# T_STorM32_motor_v24E.net
KiCad netlist of a schematic drawn in EAGLE
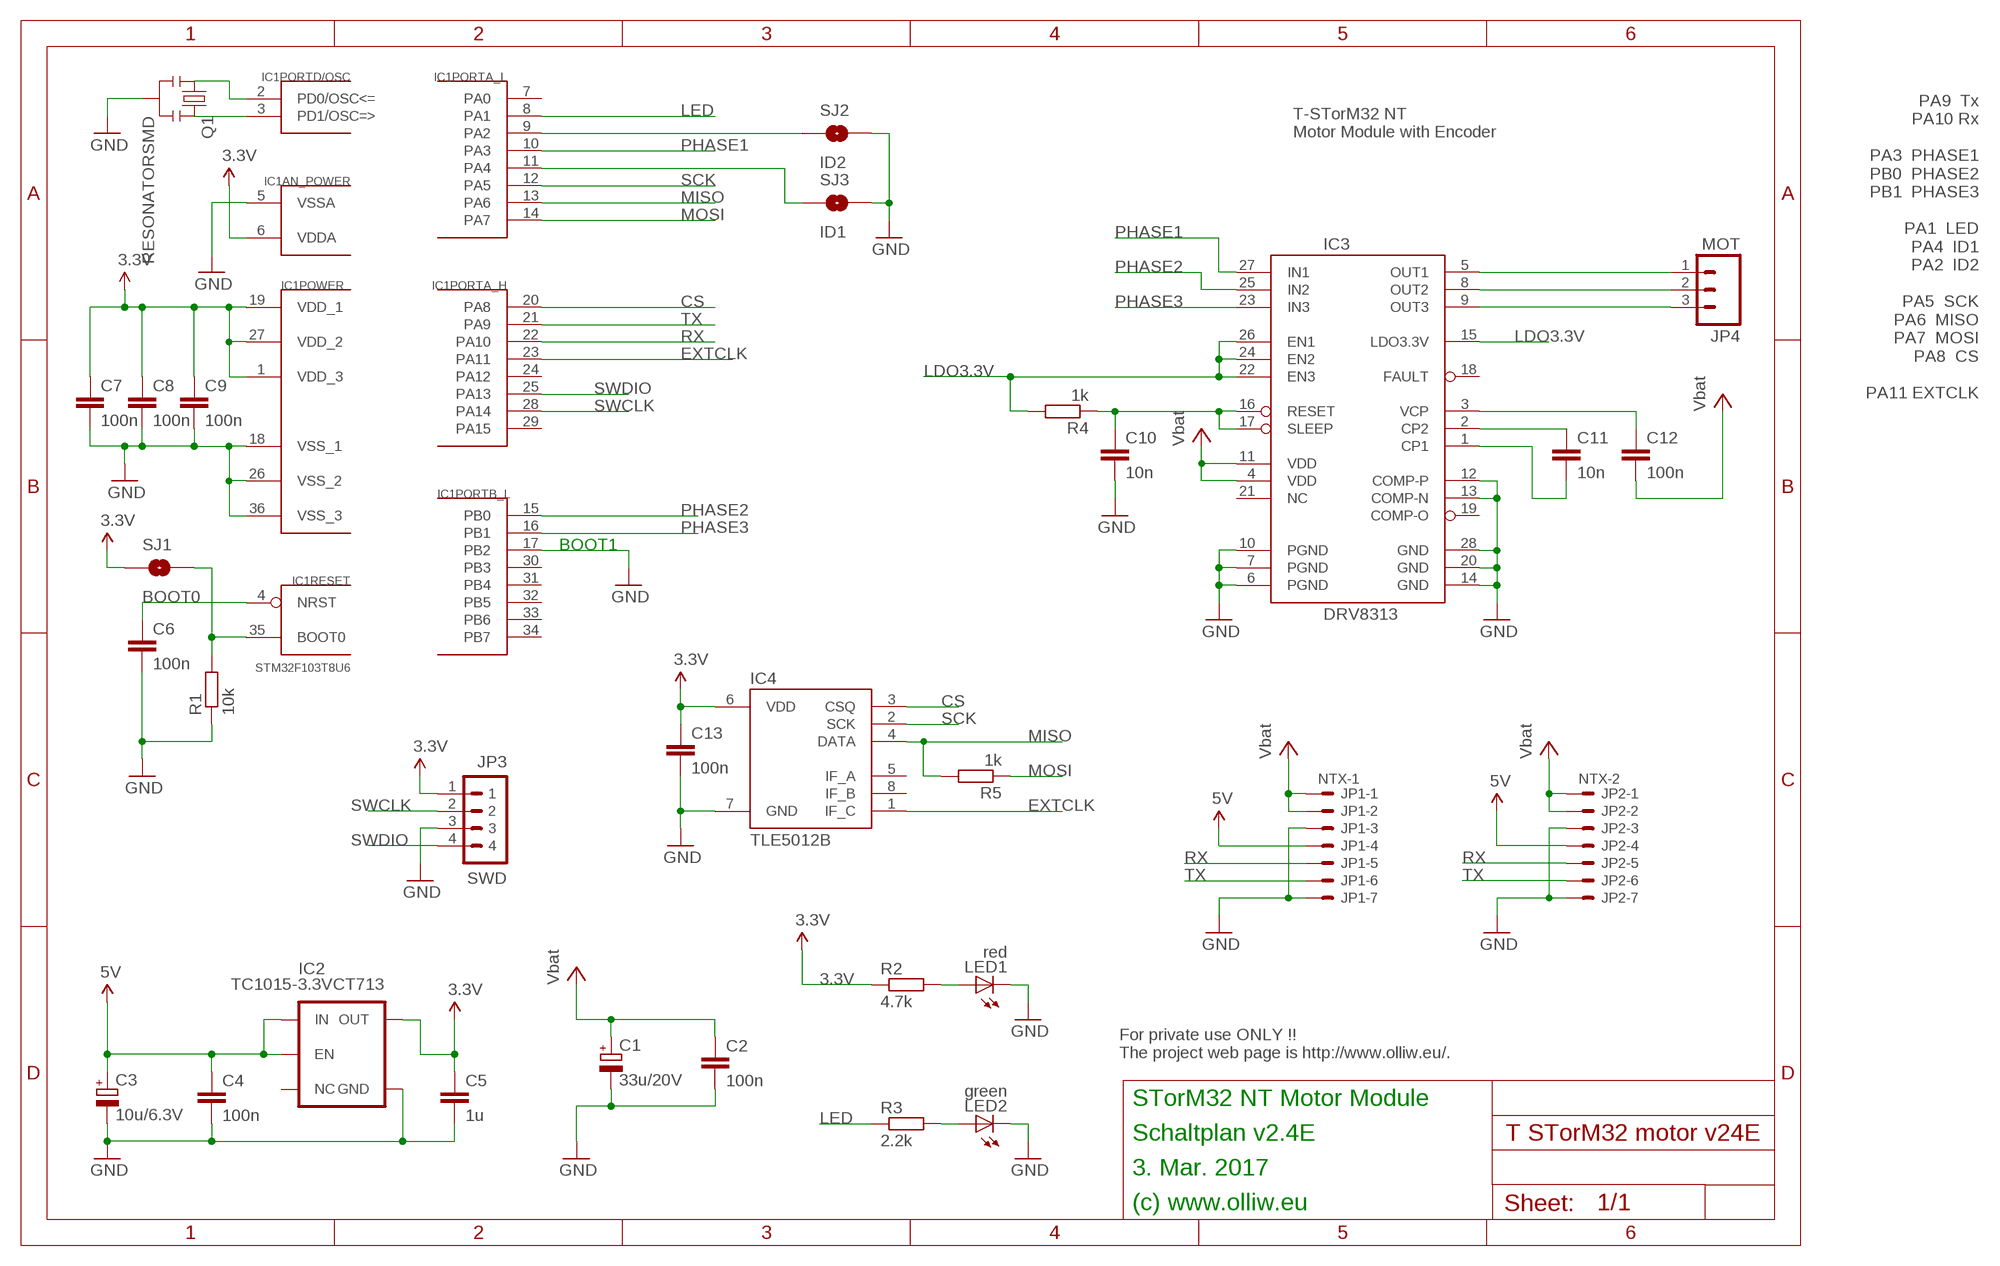
[diagram p0: schematic, sheet 1]

(export (version "E")
  (design (tool "Eeschema 10.0.6"))
  (components
    (comp (ref "C1")
      (value "33u/20V")
      (footprint "eagle-import:SMC_C")
      (libsource (lib "eagle-import") (part "CPOL-EUSMCC"))
    )
    (comp (ref "C2")
      (value "100n")
      (footprint "eagle-import:C0603")
      (libsource (lib "eagle-import") (part "C-EUC0603"))
    )
    (comp (ref "C3")
      (value "10u/6.3V")
      (footprint "eagle-import:SMC_B")
      (libsource (lib "eagle-import") (part "CPOL-EUSMCB"))
    )
    (comp (ref "C4")
      (value "100n")
      (footprint "eagle-import:C0603")
      (libsource (lib "eagle-import") (part "C-EUC0603"))
    )
    (comp (ref "C5")
      (value "1u")
      (footprint "eagle-import:C0603")
      (libsource (lib "eagle-import") (part "C-EUC0603"))
    )
    (comp (ref "C6")
      (value "100n")
      (footprint "eagle-import:C0603")
      (libsource (lib "eagle-import") (part "C-EUC0603"))
    )
    (comp (ref "C7")
      (value "100n")
      (footprint "eagle-import:C0603")
      (libsource (lib "eagle-import") (part "C-EUC0603"))
    )
    (comp (ref "C8")
      (value "100n")
      (footprint "eagle-import:C0603")
      (libsource (lib "eagle-import") (part "C-EUC0603"))
    )
    (comp (ref "C9")
      (value "100n")
      (footprint "eagle-import:C0603")
      (libsource (lib "eagle-import") (part "C-EUC0603"))
    )
    (comp (ref "C10")
      (value "10n")
      (footprint "eagle-import:C0603")
      (libsource (lib "eagle-import") (part "C-EUC0603"))
    )
    (comp (ref "C11")
      (value "10n")
      (footprint "eagle-import:C0603")
      (libsource (lib "eagle-import") (part "C-EUC0603"))
    )
    (comp (ref "C12")
      (value "100n")
      (footprint "eagle-import:C0603")
      (libsource (lib "eagle-import") (part "C-EUC0603"))
    )
    (comp (ref "C13")
      (value "100n")
      (footprint "eagle-import:C0603")
      (libsource (lib "eagle-import") (part "C-EUC0603"))
    )
    (comp (ref "IC1")
      (value "STM32F103T8U6")
      (footprint "eagle-import:VFQFPN36")
      (libsource (lib "eagle-import") (part "STM32F10XTXU6"))
    )
    (comp (ref "IC2")
      (value "TC1015-3.3VCT713")
      (footprint "eagle-import:SOT23-5")
      (libsource (lib "eagle-import") (part "V_REG_TPS76433SOT23-5"))
    )
    (comp (ref "IC3")
      (value "DRV8313")
      (footprint "eagle-import:HTSSOP28")
      (libsource (lib "eagle-import") (part "DRV8313"))
    )
    (comp (ref "IC4")
      (value "TLE5012B")
      (footprint "eagle-import:SO08")
      (libsource (lib "eagle-import") (part "TLE5012B"))
    )
    (comp (ref "JP1")
      (value "NTX-1")
      (footprint "eagle-import:SM07B-SRSS-TB")
      (libsource (lib "eagle-import") (part "?M07B-SRSS-TBS"))
    )
    (comp (ref "JP2")
      (value "NTX-2")
      (footprint "eagle-import:SM07B-SRSS-TB")
      (libsource (lib "eagle-import") (part "?M07B-SRSS-TBS"))
    )
    (comp (ref "JP3")
      (value "SWD")
      (footprint "eagle-import:4X1_1P27_OCT_BILEX")
      (libsource (lib "eagle-import") (part "P4X1_1P27-OCT_BILEX"))
    )
    (comp (ref "JP4")
      (value "MOT")
      (footprint "eagle-import:1X03")
      (libsource (lib "eagle-import") (part "M03PTH"))
    )
    (comp (ref "LED1")
      (value "red")
      (footprint "eagle-import:CHIPLED_0603")
      (libsource (lib "eagle-import") (part "LEDCHIPLED_0603"))
    )
    (comp (ref "LED2")
      (value "green")
      (footprint "eagle-import:CHIPLED_0603")
      (libsource (lib "eagle-import") (part "LEDCHIPLED_0603"))
    )
    (comp (ref "Q1")
      (value "RESONATORSMD")
      (footprint "eagle-import:RESONATOR-SMD")
      (libsource (lib "eagle-import") (part "RESONATORSMD"))
    )
    (comp (ref "R1")
      (value "10k")
      (footprint "eagle-import:R0603")
      (libsource (lib "eagle-import") (part "R-EU_R0603"))
    )
    (comp (ref "R2")
      (value "4.7k")
      (footprint "eagle-import:R0603")
      (libsource (lib "eagle-import") (part "R-EU_R0603"))
    )
    (comp (ref "R3")
      (value "2.2k")
      (footprint "eagle-import:R0603")
      (libsource (lib "eagle-import") (part "R-EU_R0603"))
    )
    (comp (ref "R4")
      (value "1k")
      (footprint "eagle-import:R0603")
      (libsource (lib "eagle-import") (part "R-EU_R0603"))
    )
    (comp (ref "R5")
      (value "1k")
      (footprint "eagle-import:R0603")
      (libsource (lib "eagle-import") (part "R-EU_R0603"))
    )
    (comp (ref "SJ1")
      (value "BOOT0")
      (footprint "eagle-import:SJ_2S-NO")
      (libsource (lib "eagle-import") (part "SOLDERJUMPERNO"))
    )
    (comp (ref "SJ2")
      (value "ID2")
      (footprint "eagle-import:SJ_2S-NO")
      (libsource (lib "eagle-import") (part "SOLDERJUMPERNO"))
    )
    (comp (ref "SJ3")
      (value "ID1")
      (footprint "eagle-import:SJ_2S-NO")
      (libsource (lib "eagle-import") (part "SOLDERJUMPERNO"))
    )
  )
  (nets
    (net (code "1") (name "/CS") (class "Default")
      (node (ref "IC1") (pin "20") (pinfunction "PA8_20") (pintype "bidirectional"))
      (node (ref "IC4") (pin "3") (pinfunction "CSQ_3") (pintype "input"))
    )
    (net (code "2") (name "/EXTCLK") (class "Default")
      (node (ref "IC1") (pin "23") (pinfunction "PA11_23") (pintype "bidirectional"))
      (node (ref "IC4") (pin "1") (pinfunction "IF_C_1") (pintype "bidirectional"))
    )
    (net (code "3") (name "/LDO3.3V") (class "Default")
      (node (ref "IC3") (pin "15") (pinfunction "LDO3.3V_15") (pintype "output"))
      (node (ref "IC3") (pin "22") (pinfunction "EN3_22") (pintype "input"))
      (node (ref "IC3") (pin "24") (pinfunction "EN2_24") (pintype "input"))
      (node (ref "IC3") (pin "26") (pinfunction "EN1_26") (pintype "input"))
      (node (ref "R4") (pin "2") (pinfunction "2_2") (pintype "passive"))
    )
    (net (code "4") (name "/LED") (class "Default")
      (node (ref "IC1") (pin "8") (pinfunction "PA1_8") (pintype "bidirectional"))
      (node (ref "R3") (pin "1") (pinfunction "1_1") (pintype "passive"))
    )
    (net (code "5") (name "/MISO") (class "Default")
      (node (ref "IC1") (pin "13") (pinfunction "PA6_13") (pintype "bidirectional"))
      (node (ref "IC4") (pin "4") (pinfunction "DATA_4") (pintype "bidirectional"))
      (node (ref "R5") (pin "2") (pinfunction "2_2") (pintype "passive"))
    )
    (net (code "6") (name "/MOSI") (class "Default")
      (node (ref "IC1") (pin "14") (pinfunction "PA7_14") (pintype "bidirectional"))
      (node (ref "R5") (pin "1") (pinfunction "1_1") (pintype "passive"))
    )
    (net (code "7") (name "/PHASE1") (class "Default")
      (node (ref "IC1") (pin "10") (pinfunction "PA3_10") (pintype "bidirectional"))
      (node (ref "IC3") (pin "27") (pinfunction "IN1_27") (pintype "input"))
    )
    (net (code "8") (name "/PHASE2") (class "Default")
      (node (ref "IC1") (pin "15") (pinfunction "PB0_15") (pintype "bidirectional"))
      (node (ref "IC3") (pin "25") (pinfunction "IN2_25") (pintype "input"))
    )
    (net (code "9") (name "/PHASE3") (class "Default")
      (node (ref "IC1") (pin "16") (pinfunction "PB1_16") (pintype "bidirectional"))
      (node (ref "IC3") (pin "23") (pinfunction "IN3_23") (pintype "input"))
    )
    (net (code "10") (name "/RX") (class "Default")
      (node (ref "IC1") (pin "22") (pinfunction "PA10_22") (pintype "bidirectional"))
      (node (ref "JP1") (pin "5") (pinfunction "S_5") (pintype "passive"))
      (node (ref "JP2") (pin "5") (pinfunction "S_5") (pintype "passive"))
    )
    (net (code "11") (name "/SCK") (class "Default")
      (node (ref "IC1") (pin "12") (pinfunction "PA5_12") (pintype "bidirectional"))
      (node (ref "IC4") (pin "2") (pinfunction "SCK_2") (pintype "input"))
    )
    (net (code "12") (name "/SWCLK") (class "Default")
      (node (ref "IC1") (pin "28") (pinfunction "PA14_28") (pintype "bidirectional"))
      (node (ref "JP3") (pin "2") (pinfunction "2_2") (pintype "passive"))
    )
    (net (code "13") (name "/SWDIO") (class "Default")
      (node (ref "IC1") (pin "25") (pinfunction "PA13_25") (pintype "bidirectional"))
      (node (ref "JP3") (pin "4") (pinfunction "4_4") (pintype "passive"))
    )
    (net (code "14") (name "/TX") (class "Default")
      (node (ref "IC1") (pin "21") (pinfunction "PA9_21") (pintype "bidirectional"))
      (node (ref "JP1") (pin "6") (pinfunction "S_6") (pintype "passive"))
      (node (ref "JP2") (pin "6") (pinfunction "S_6") (pintype "passive"))
    )
    (net (code "15") (name "3.3V") (class "Default")
      (node (ref "C13") (pin "1") (pinfunction "1_1") (pintype "passive"))
      (node (ref "C5") (pin "1") (pinfunction "1_1") (pintype "passive"))
      (node (ref "C7") (pin "1") (pinfunction "1_1") (pintype "passive"))
      (node (ref "C8") (pin "1") (pinfunction "1_1") (pintype "passive"))
      (node (ref "C9") (pin "1") (pinfunction "1_1") (pintype "passive"))
      (node (ref "IC1") (pin "1") (pinfunction "VDD_3_1") (pintype "power_in"))
      (node (ref "IC1") (pin "19") (pinfunction "VDD_1_19") (pintype "power_in"))
      (node (ref "IC1") (pin "27") (pinfunction "VDD_2_27") (pintype "power_in"))
      (node (ref "IC1") (pin "6") (pinfunction "VDDA_6") (pintype "power_in"))
      (node (ref "IC2") (pin "5") (pinfunction "OUT_5") (pintype "passive"))
      (node (ref "IC4") (pin "6") (pinfunction "VDD_6") (pintype "power_in"))
      (node (ref "JP3") (pin "1") (pinfunction "1_1") (pintype "passive"))
      (node (ref "R2") (pin "1") (pinfunction "1_1") (pintype "passive"))
      (node (ref "SJ1") (pin "1") (pinfunction "1_1") (pintype "passive"))
    )
    (net (code "16") (name "5V") (class "Default")
      (node (ref "C3") (pin "+") (pinfunction "+_+") (pintype "passive"))
      (node (ref "C4") (pin "1") (pinfunction "1_1") (pintype "passive"))
      (node (ref "IC2") (pin "1") (pinfunction "IN_1") (pintype "input"))
      (node (ref "IC2") (pin "3") (pinfunction "EN_3") (pintype "input"))
      (node (ref "JP1") (pin "4") (pinfunction "S_4") (pintype "passive"))
      (node (ref "JP2") (pin "4") (pinfunction "S_4") (pintype "passive"))
    )
    (net (code "17") (name "GND") (class "Default")
      (node (ref "C1") (pin "-") (pinfunction "-_-") (pintype "passive"))
      (node (ref "C10") (pin "2") (pinfunction "2_2") (pintype "passive"))
      (node (ref "C13") (pin "2") (pinfunction "2_2") (pintype "passive"))
      (node (ref "C2") (pin "2") (pinfunction "2_2") (pintype "passive"))
      (node (ref "C3") (pin "-") (pinfunction "-_-") (pintype "passive"))
      (node (ref "C4") (pin "2") (pinfunction "2_2") (pintype "passive"))
      (node (ref "C5") (pin "2") (pinfunction "2_2") (pintype "passive"))
      (node (ref "C6") (pin "2") (pinfunction "2_2") (pintype "passive"))
      (node (ref "C7") (pin "2") (pinfunction "2_2") (pintype "passive"))
      (node (ref "C8") (pin "2") (pinfunction "2_2") (pintype "passive"))
      (node (ref "C9") (pin "2") (pinfunction "2_2") (pintype "passive"))
      (node (ref "IC1") (pin "17") (pinfunction "PB2_17") (pintype "bidirectional"))
      (node (ref "IC1") (pin "18") (pinfunction "VSS_1_18") (pintype "power_in"))
      (node (ref "IC1") (pin "26") (pinfunction "VSS_2_26") (pintype "power_in"))
      (node (ref "IC1") (pin "36") (pinfunction "VSS_3_36") (pintype "power_in"))
      (node (ref "IC1") (pin "5") (pinfunction "VSSA_5") (pintype "power_in"))
      (node (ref "IC2") (pin "2") (pinfunction "GND_2") (pintype "input"))
      (node (ref "IC3") (pin "10") (pinfunction "PGND_10") (pintype "power_in"))
      (node (ref "IC3") (pin "12") (pinfunction "COMP-P_12") (pintype "input"))
      (node (ref "IC3") (pin "13") (pinfunction "COMP-N_13") (pintype "input"))
      (node (ref "IC3") (pin "14") (pinfunction "GND_14") (pintype "power_in"))
      (node (ref "IC3") (pin "20") (pinfunction "GND_20") (pintype "power_in"))
      (node (ref "IC3") (pin "28") (pinfunction "GND_28") (pintype "power_in"))
      (node (ref "IC3") (pin "6") (pinfunction "PGND_6") (pintype "power_in"))
      (node (ref "IC3") (pin "7") (pinfunction "PGND_7") (pintype "power_in"))
      (node (ref "IC4") (pin "7") (pinfunction "GND_7") (pintype "power_in"))
      (node (ref "JP1") (pin "3") (pinfunction "S_3") (pintype "passive"))
      (node (ref "JP1") (pin "7") (pinfunction "S_7") (pintype "passive"))
      (node (ref "JP2") (pin "3") (pinfunction "S_3") (pintype "passive"))
      (node (ref "JP2") (pin "7") (pinfunction "S_7") (pintype "passive"))
      (node (ref "JP3") (pin "3") (pinfunction "3_3") (pintype "passive"))
      (node (ref "LED1") (pin "C") (pinfunction "C_C") (pintype "passive"))
      (node (ref "LED2") (pin "C") (pinfunction "C_C") (pintype "passive"))
      (node (ref "Q1") (pin "2") (pinfunction "2_2") (pintype "passive"))
      (node (ref "R1") (pin "1") (pinfunction "1_1") (pintype "passive"))
      (node (ref "SJ2") (pin "2") (pinfunction "2_2") (pintype "passive"))
      (node (ref "SJ3") (pin "2") (pinfunction "2_2") (pintype "passive"))
    )
    (net (code "18") (name "Net-(IC1C-PA2)") (class "Default")
      (node (ref "IC1") (pin "9") (pinfunction "PA2_9") (pintype "bidirectional"))
      (node (ref "SJ2") (pin "1") (pinfunction "1_1") (pintype "passive"))
    )
    (net (code "19") (name "Net-(IC1C-PA4)") (class "Default")
      (node (ref "IC1") (pin "11") (pinfunction "PA4_11") (pintype "bidirectional"))
      (node (ref "SJ3") (pin "1") (pinfunction "1_1") (pintype "passive"))
    )
    (net (code "20") (name "Net-(IC1E-PD0{slash}OSC<=)") (class "Default")
      (node (ref "IC1") (pin "2") (pinfunction "PD0/OSC<=_2") (pintype "bidirectional"))
      (node (ref "Q1") (pin "1") (pinfunction "1_1") (pintype "passive"))
    )
    (net (code "21") (name "Net-(IC1E-PD1{slash}OSC=>)") (class "Default")
      (node (ref "IC1") (pin "3") (pinfunction "PD1/OSC=>_3") (pintype "bidirectional"))
      (node (ref "Q1") (pin "3") (pinfunction "3_3") (pintype "passive"))
    )
    (net (code "22") (name "Net-(IC1G-BOOT0)") (class "Default")
      (node (ref "IC1") (pin "35") (pinfunction "BOOT0_35") (pintype "input"))
      (node (ref "R1") (pin "2") (pinfunction "2_2") (pintype "passive"))
      (node (ref "SJ1") (pin "2") (pinfunction "2_2") (pintype "passive"))
    )
    (net (code "23") (name "Net-(IC1G-NRST)") (class "Default")
      (node (ref "C6") (pin "1") (pinfunction "1_1") (pintype "passive"))
      (node (ref "IC1") (pin "4") (pinfunction "NRST_4") (pintype "input"))
    )
    (net (code "24") (name "Net-(IC3-CP1)") (class "Default")
      (node (ref "C11") (pin "2") (pinfunction "2_2") (pintype "passive"))
      (node (ref "IC3") (pin "1") (pinfunction "CP1_1") (pintype "bidirectional"))
    )
    (net (code "25") (name "Net-(IC3-CP2)") (class "Default")
      (node (ref "C11") (pin "1") (pinfunction "1_1") (pintype "passive"))
      (node (ref "IC3") (pin "2") (pinfunction "CP2_2") (pintype "bidirectional"))
    )
    (net (code "26") (name "Net-(IC3-OUT1)") (class "Default")
      (node (ref "IC3") (pin "5") (pinfunction "OUT1_5") (pintype "output"))
      (node (ref "JP4") (pin "1") (pinfunction "1_1") (pintype "passive"))
    )
    (net (code "27") (name "Net-(IC3-OUT2)") (class "Default")
      (node (ref "IC3") (pin "8") (pinfunction "OUT2_8") (pintype "output"))
      (node (ref "JP4") (pin "2") (pinfunction "2_2") (pintype "passive"))
    )
    (net (code "28") (name "Net-(IC3-OUT3)") (class "Default")
      (node (ref "IC3") (pin "9") (pinfunction "OUT3_9") (pintype "output"))
      (node (ref "JP4") (pin "3") (pinfunction "3_3") (pintype "passive"))
    )
    (net (code "29") (name "Net-(IC3-RESET)") (class "Default")
      (node (ref "C10") (pin "1") (pinfunction "1_1") (pintype "passive"))
      (node (ref "IC3") (pin "16") (pinfunction "RESET_16") (pintype "input"))
      (node (ref "IC3") (pin "17") (pinfunction "SLEEP_17") (pintype "input"))
      (node (ref "R4") (pin "1") (pinfunction "1_1") (pintype "passive"))
    )
    (net (code "30") (name "Net-(IC3-VCP)") (class "Default")
      (node (ref "C12") (pin "1") (pinfunction "1_1") (pintype "passive"))
      (node (ref "IC3") (pin "3") (pinfunction "VCP_3") (pintype "bidirectional"))
    )
    (net (code "31") (name "Net-(LED1-PadA)") (class "Default")
      (node (ref "LED1") (pin "A") (pinfunction "A_A") (pintype "passive"))
      (node (ref "R2") (pin "2") (pinfunction "2_2") (pintype "passive"))
    )
    (net (code "32") (name "Net-(LED2-PadA)") (class "Default")
      (node (ref "LED2") (pin "A") (pinfunction "A_A") (pintype "passive"))
      (node (ref "R3") (pin "2") (pinfunction "2_2") (pintype "passive"))
    )
    (net (code "33") (name "Vbat") (class "Default")
      (node (ref "C1") (pin "+") (pinfunction "+_+") (pintype "passive"))
      (node (ref "C12") (pin "2") (pinfunction "2_2") (pintype "passive"))
      (node (ref "C2") (pin "1") (pinfunction "1_1") (pintype "passive"))
      (node (ref "IC3") (pin "11") (pinfunction "VDD_11") (pintype "power_in"))
      (node (ref "IC3") (pin "4") (pinfunction "VDD_4") (pintype "power_in"))
      (node (ref "JP1") (pin "1") (pinfunction "S_1") (pintype "passive"))
      (node (ref "JP1") (pin "2") (pinfunction "S_2") (pintype "passive"))
      (node (ref "JP2") (pin "1") (pinfunction "S_1") (pintype "passive"))
      (node (ref "JP2") (pin "2") (pinfunction "S_2") (pintype "passive"))
    )
    (net (code "34") (name "unconnected-(IC1B-PA12-Pad24)") (class "Default")
      (node (ref "IC1") (pin "24") (pinfunction "PA12_24") (pintype "bidirectional"))
    )
    (net (code "35") (name "unconnected-(IC1B-PA15-Pad29)") (class "Default")
      (node (ref "IC1") (pin "29") (pinfunction "PA15_29") (pintype "bidirectional"))
    )
    (net (code "36") (name "unconnected-(IC1C-PA0-Pad7)") (class "Default")
      (node (ref "IC1") (pin "7") (pinfunction "PA0_7") (pintype "bidirectional"))
    )
    (net (code "37") (name "unconnected-(IC1D-PB3-Pad30)") (class "Default")
      (node (ref "IC1") (pin "30") (pinfunction "PB3_30") (pintype "bidirectional"))
    )
    (net (code "38") (name "unconnected-(IC1D-PB4-Pad31)") (class "Default")
      (node (ref "IC1") (pin "31") (pinfunction "PB4_31") (pintype "bidirectional"))
    )
    (net (code "39") (name "unconnected-(IC1D-PB5-Pad32)") (class "Default")
      (node (ref "IC1") (pin "32") (pinfunction "PB5_32") (pintype "bidirectional"))
    )
    (net (code "40") (name "unconnected-(IC1D-PB6-Pad33)") (class "Default")
      (node (ref "IC1") (pin "33") (pinfunction "PB6_33") (pintype "bidirectional"))
    )
    (net (code "41") (name "unconnected-(IC1D-PB7-Pad34)") (class "Default")
      (node (ref "IC1") (pin "34") (pinfunction "PB7_34") (pintype "bidirectional"))
    )
    (net (code "42") (name "unconnected-(IC2-NC-Pad4)") (class "Default")
      (node (ref "IC2") (pin "4") (pinfunction "NC_4") (pintype "input"))
    )
    (net (code "43") (name "unconnected-(IC3-COMP-O-Pad19)") (class "Default")
      (node (ref "IC3") (pin "19") (pinfunction "COMP-O_19") (pintype "output"))
    )
    (net (code "44") (name "unconnected-(IC3-FAULT-Pad18)") (class "Default")
      (node (ref "IC3") (pin "18") (pinfunction "FAULT_18") (pintype "output"))
    )
    (net (code "45") (name "unconnected-(IC3-NC-Pad21)") (class "Default")
      (node (ref "IC3") (pin "21") (pinfunction "NC_21") (pintype "no_connect"))
    )
    (net (code "46") (name "unconnected-(IC4-IF_A-Pad5)") (class "Default")
      (node (ref "IC4") (pin "5") (pinfunction "IF_A_5") (pintype "bidirectional"))
    )
    (net (code "47") (name "unconnected-(IC4-IF_B-Pad8)") (class "Default")
      (node (ref "IC4") (pin "8") (pinfunction "IF_B_8") (pintype "output"))
    )
  )
)
